# Fihl54-xtalOven.net
KiCad netlist of a schematic drawn in EAGLE
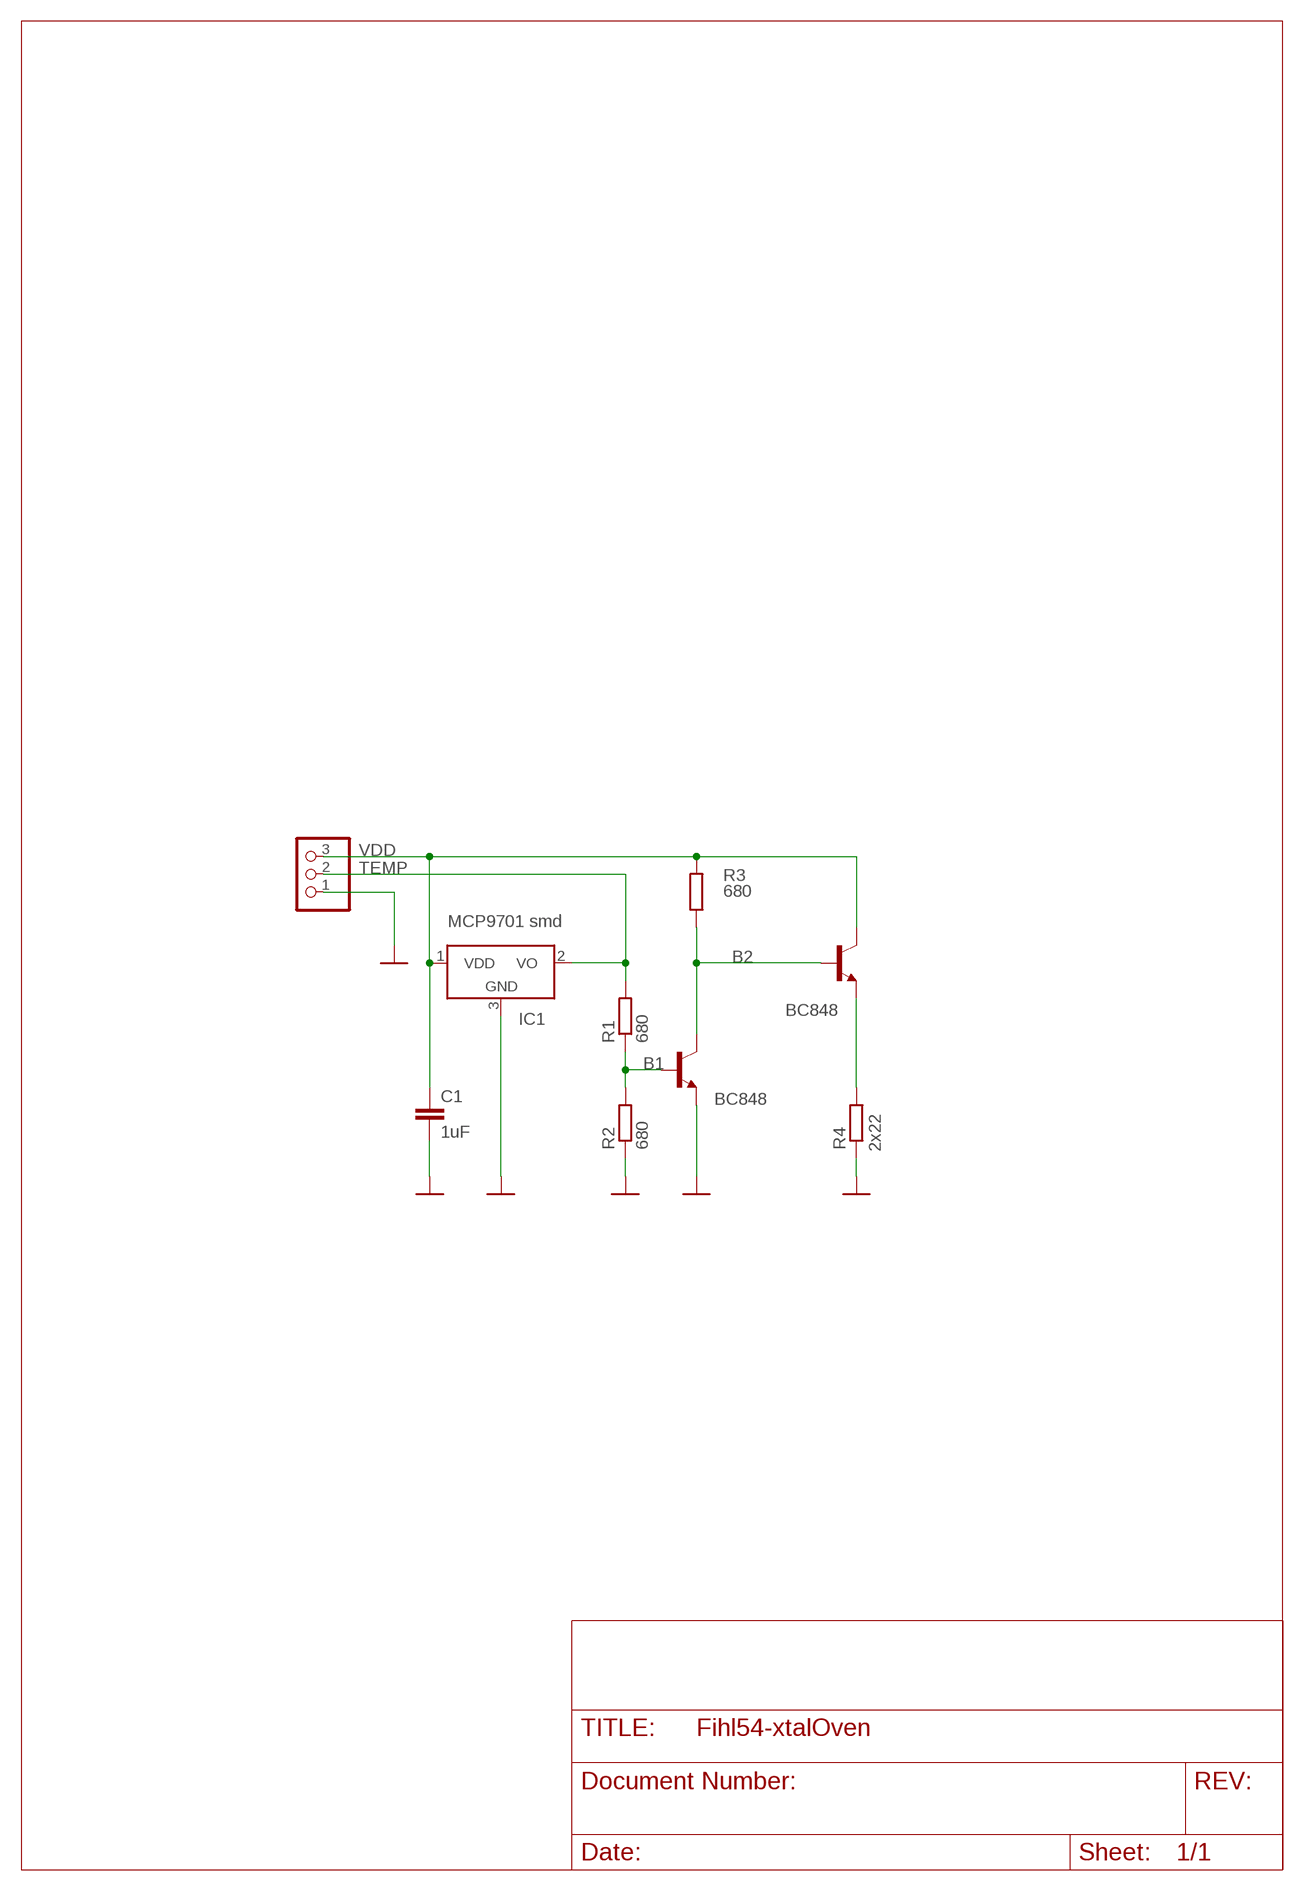
[diagram p0: schematic, sheet 1]

(export (version "E")
  (design (tool "Eeschema 10.0.6"))
  (components
    (comp (ref "C1")
      (value "1uF")
      (footprint "eagle-import:C1210")
      (libsource (lib "eagle-import") (part "CAPX5R"))
    )
    (comp (ref "IC1")
      (value "MCP9701 smd")
      (footprint "eagle-import:SOT23-3")
      (libsource (lib "eagle-import") (part "MCP9700T"))
    )
    (comp (ref "JP1")
      (value "jp1")
      (footprint "eagle-import:1X03")
      (libsource (lib "eagle-import") (part "PINHD-1X3"))
    )
    (comp (ref "R1")
      (value "680")
      (footprint "eagle-import:M1206")
      (libsource (lib "eagle-import") (part "R-EU_M1206"))
    )
    (comp (ref "R2")
      (value "680")
      (footprint "eagle-import:M1206")
      (libsource (lib "eagle-import") (part "R-EU_M1206"))
    )
    (comp (ref "R3")
      (value "680")
      (footprint "eagle-import:M1206")
      (libsource (lib "eagle-import") (part "R-EU_M1206"))
    )
    (comp (ref "R4")
      (value "2x22")
      (footprint "eagle-import:M1206")
      (libsource (lib "eagle-import") (part "R-EU_M1206"))
    )
    (comp (ref "T1")
      (value "BC848")
      (footprint "eagle-import:SOT23")
      (libsource (lib "eagle-import") (part "BC848"))
    )
    (comp (ref "T2")
      (value "BC848")
      (footprint "eagle-import:SOT23")
      (libsource (lib "eagle-import") (part "BC848"))
    )
  )
  (nets
    (net (code "1") (name "/B1") (class "Default")
      (node (ref "R1") (pin "1") (pinfunction "1_1") (pintype "passive"))
      (node (ref "R2") (pin "2") (pinfunction "2_2") (pintype "passive"))
      (node (ref "T1") (pin "1") (pinfunction "B_1") (pintype "passive"))
    )
    (net (code "2") (name "/B2") (class "Default")
      (node (ref "R3") (pin "1") (pinfunction "1_1") (pintype "passive"))
      (node (ref "T1") (pin "3") (pinfunction "C_3") (pintype "passive"))
      (node (ref "T2") (pin "1") (pinfunction "B_1") (pintype "passive"))
    )
    (net (code "3") (name "/TEMP") (class "Default")
      (node (ref "IC1") (pin "2") (pinfunction "VO_2") (pintype "bidirectional"))
      (node (ref "JP1") (pin "2") (pinfunction "2_2") (pintype "passive"))
      (node (ref "R1") (pin "2") (pinfunction "2_2") (pintype "passive"))
    )
    (net (code "4") (name "/VDD") (class "Default")
      (node (ref "C1") (pin "1") (pinfunction "1_1") (pintype "passive"))
      (node (ref "IC1") (pin "1") (pinfunction "VDD_1") (pintype "power_in"))
      (node (ref "JP1") (pin "3") (pinfunction "3_3") (pintype "passive"))
      (node (ref "R3") (pin "2") (pinfunction "2_2") (pintype "passive"))
      (node (ref "T2") (pin "3") (pinfunction "C_3") (pintype "passive"))
    )
    (net (code "5") (name "GND") (class "Default")
      (node (ref "C1") (pin "2") (pinfunction "2_2") (pintype "passive"))
      (node (ref "IC1") (pin "3") (pinfunction "GND_3") (pintype "power_in"))
      (node (ref "JP1") (pin "1") (pinfunction "1_1") (pintype "passive"))
      (node (ref "R2") (pin "1") (pinfunction "1_1") (pintype "passive"))
      (node (ref "R4") (pin "1") (pinfunction "1_1") (pintype "passive"))
      (node (ref "T1") (pin "2") (pinfunction "E_2") (pintype "passive"))
    )
    (net (code "6") (name "Net-(T2-E)") (class "Default")
      (node (ref "R4") (pin "2") (pinfunction "2_2") (pintype "passive"))
      (node (ref "T2") (pin "2") (pinfunction "E_2") (pintype "passive"))
    )
  )
)
